# 8_Inputs_8_Outputs_Card.net
KiCad netlist of a schematic drawn in EasyEDA
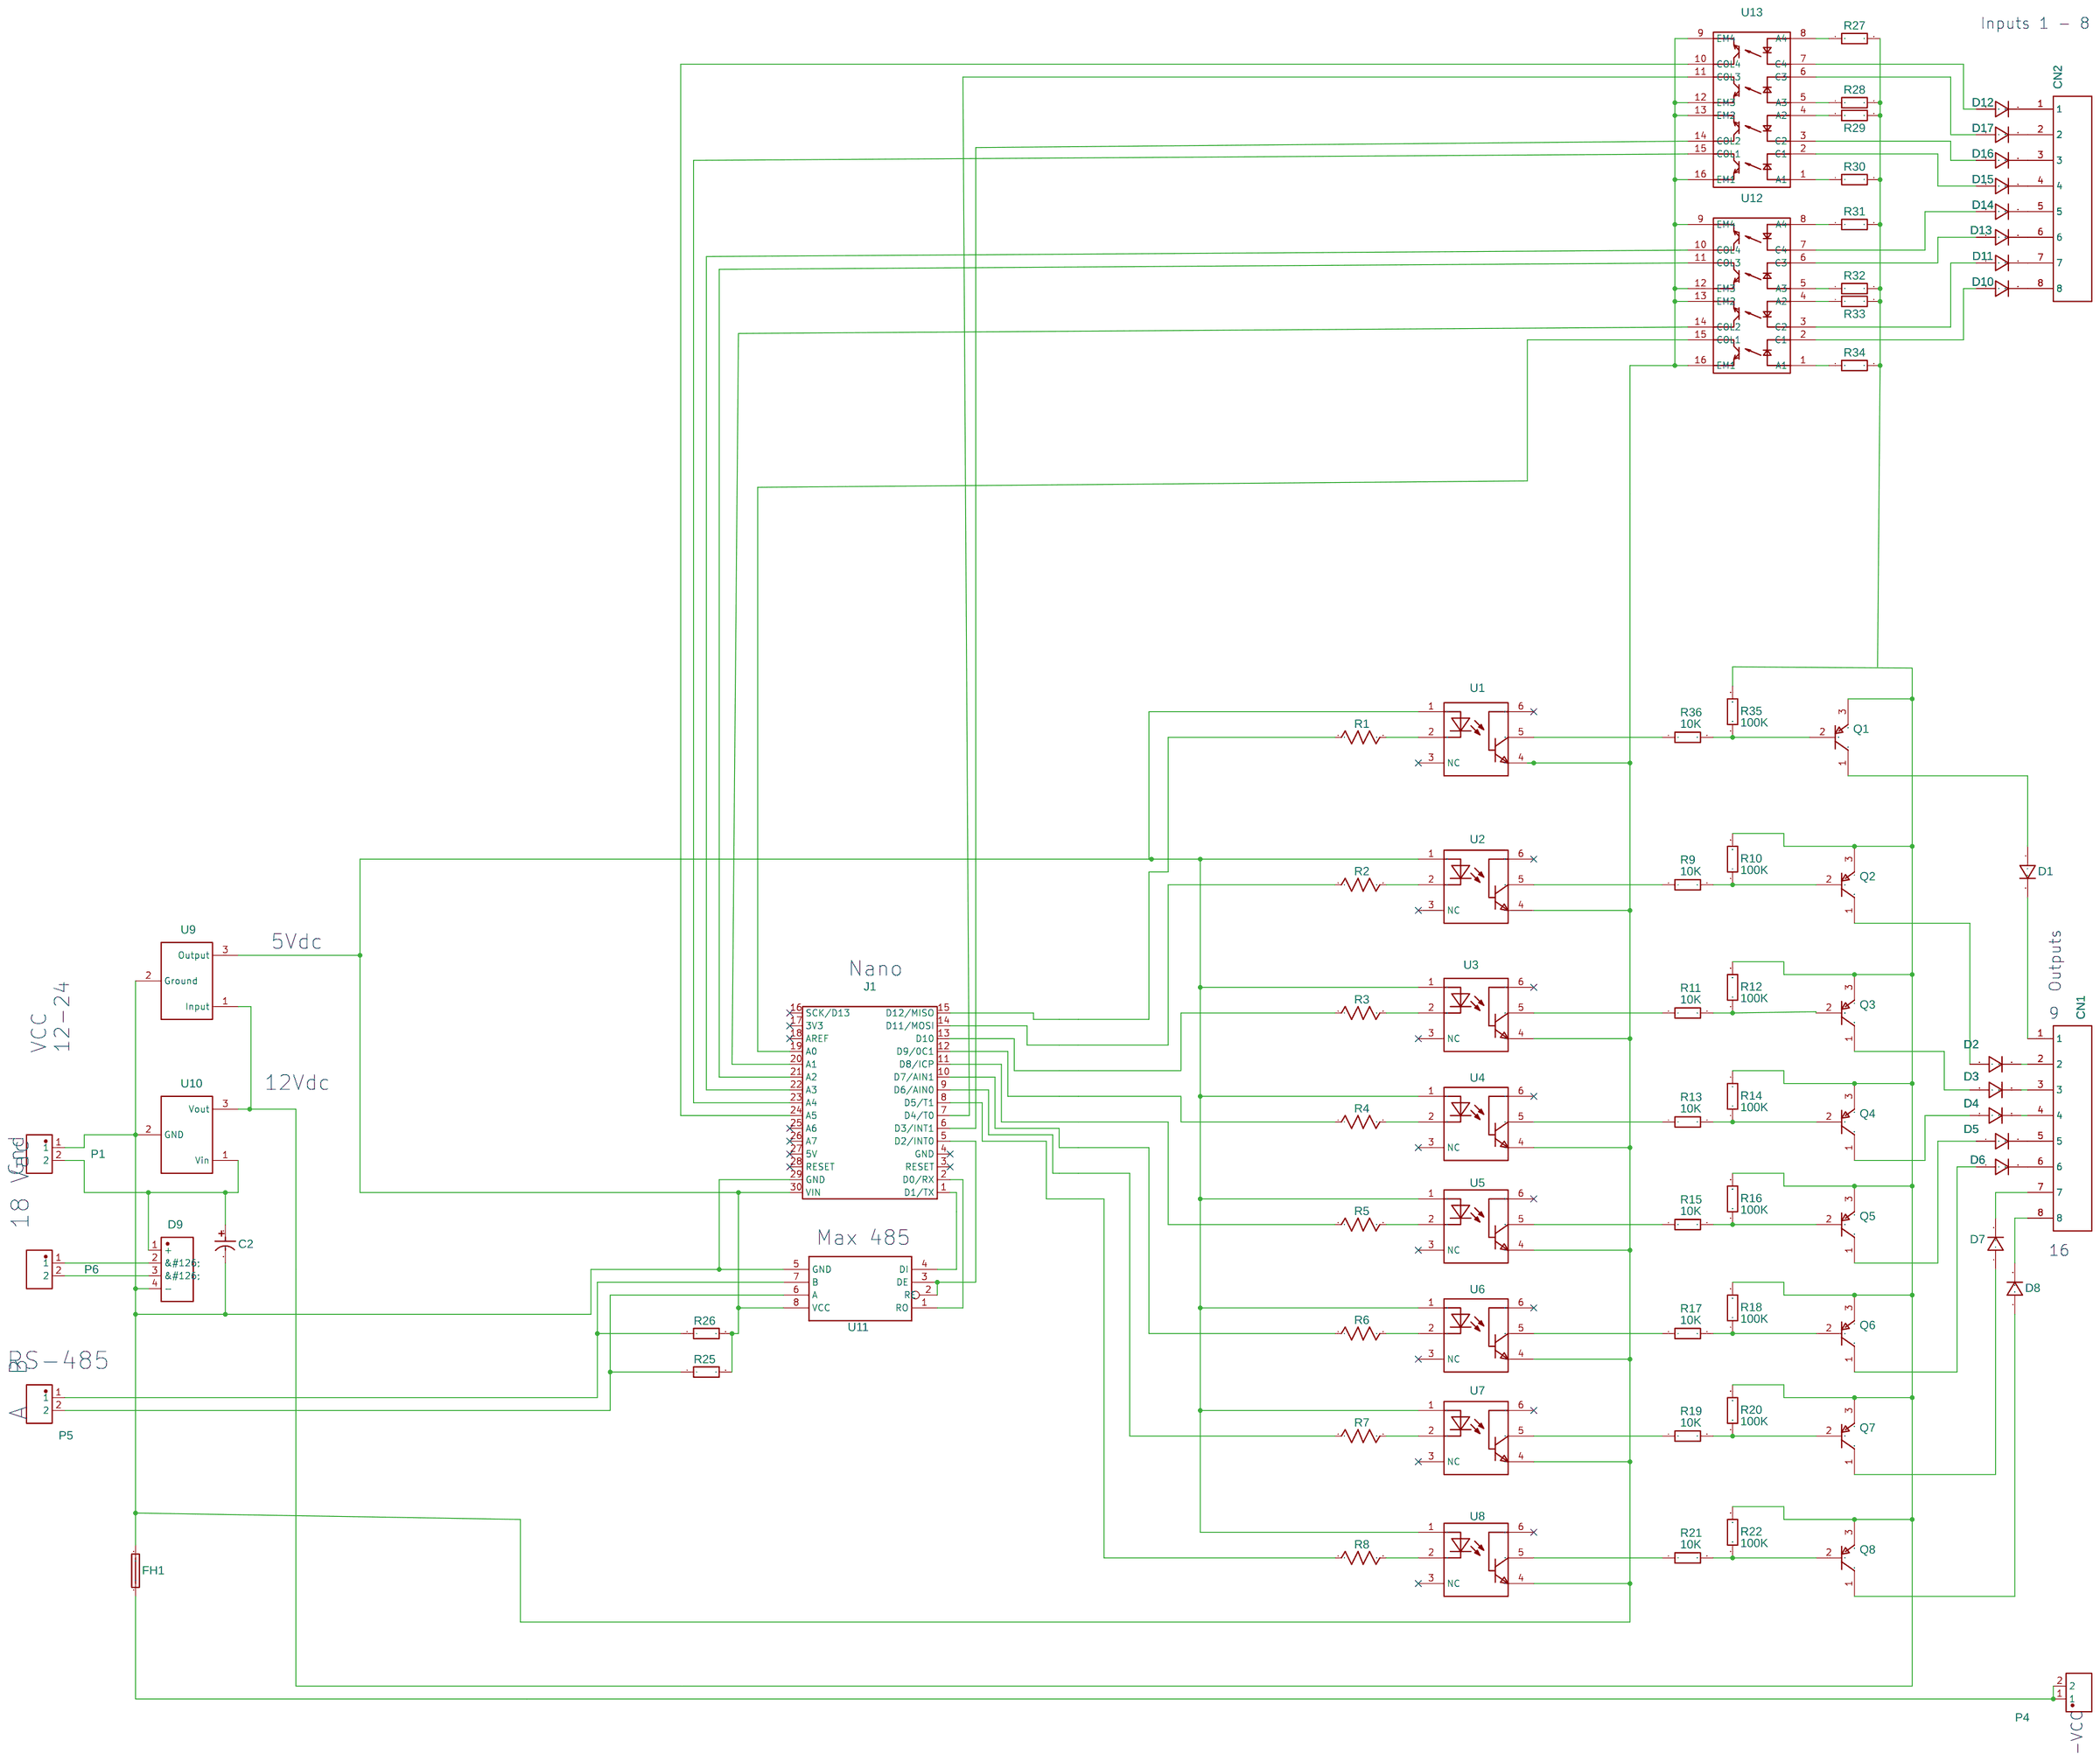
[diagram p0: schematic sheet]

(export (version "E")
  (design (tool "Eeschema 10.0.6"))
  (components
    (comp (ref "C2")
      (value "470uF")
      (fields
        (field (name "BOM_Manufacturer Part") "470uF 100V 16*25")
        (field (name "BOM_Supplier Part") "C72551")
      )
      (libsource (lib "") (part "470uF 100V 16*25"))
    )
    (comp (ref "CN1")
      (value "WJ25C-B-7.62-8P-13-00A")
      (fields (field (name "BOM_Supplier Part") "C49492"))
      (libsource (lib "") (part "Unknown_1530_395"))
    )
    (comp (ref "CN2")
      (value "WJ25C-B-7.62-8P-13-00A")
      (fields (field (name "BOM_Supplier Part") "C49492"))
      (libsource (lib "") (part "Unknown_1530_-330"))
    )
    (comp (ref "D1")
      (value "1N4001")
      (fields (field (name "BOM_Supplier Part") "C169150"))
      (libsource (lib "") (part "Unknown_1510_195"))
    )
    (comp (ref "D2")
      (value "1N4001")
      (fields (field (name "BOM_Supplier Part") "C169150"))
      (libsource (lib "") (part "Unknown_1485_345"))
    )
    (comp (ref "D3")
      (value "1N4001")
      (fields (field (name "BOM_Supplier Part") "C169150"))
      (libsource (lib "") (part "Unknown_1485_365"))
    )
    (comp (ref "D4")
      (value "1N4001")
      (fields (field (name "BOM_Supplier Part") "C169150"))
      (libsource (lib "") (part "Unknown_1485_385"))
    )
    (comp (ref "D5")
      (value "1N4001")
      (fields (field (name "BOM_Supplier Part") "C169150"))
      (libsource (lib "") (part "Unknown_1490_405"))
    )
    (comp (ref "D6")
      (value "1N4001")
      (fields (field (name "BOM_Supplier Part") "C169150"))
      (libsource (lib "") (part "Unknown_1490_425"))
    )
    (comp (ref "D7")
      (value "1N4001")
      (fields (field (name "BOM_Supplier Part") "C169150"))
      (libsource (lib "") (part "Unknown_1485_485"))
    )
    (comp (ref "D8")
      (value "1N4001")
      (fields (field (name "BOM_Supplier Part") "C169150"))
      (libsource (lib "") (part "Unknown_1500_520"))
    )
    (comp (ref "D9")
      (value "D50SB100")
      (fields (field (name "BOM_Supplier Part") "C411148"))
      (libsource (lib "") (part "Unknown_60_505"))
    )
    (comp (ref "D10")
      (value "1N4001")
      (fields (field (name "BOM_Supplier Part") "C169150"))
      (libsource (lib "") (part "Unknown_1490_-260"))
    )
    (comp (ref "D11")
      (value "1N4001")
      (fields (field (name "BOM_Supplier Part") "C169150"))
      (libsource (lib "") (part "Unknown_1490_-280"))
    )
    (comp (ref "D12")
      (value "1N4001")
      (fields (field (name "BOM_Supplier Part") "C169150"))
      (libsource (lib "") (part "Unknown_1490_-400"))
    )
    (comp (ref "D13")
      (value "1N4001")
      (fields (field (name "BOM_Supplier Part") "C169150"))
      (libsource (lib "") (part "Unknown_1490_-300"))
    )
    (comp (ref "D14")
      (value "1N4001")
      (fields (field (name "BOM_Supplier Part") "C169150"))
      (libsource (lib "") (part "Unknown_1490_-320"))
    )
    (comp (ref "D15")
      (value "1N4001")
      (fields (field (name "BOM_Supplier Part") "C169150"))
      (libsource (lib "") (part "Unknown_1490_-340"))
    )
    (comp (ref "D16")
      (value "1N4001")
      (fields (field (name "BOM_Supplier Part") "C169150"))
      (libsource (lib "") (part "Unknown_1490_-360"))
    )
    (comp (ref "D17")
      (value "1N4001")
      (fields (field (name "BOM_Supplier Part") "C169150"))
      (libsource (lib "") (part "Unknown_1490_-380"))
    )
    (comp (ref "FH1")
      (value "64600001003")
      (fields (field (name "BOM_Supplier Part") "C206887"))
      (libsource (lib "") (part "Unknown_35_740"))
    )
    (comp (ref "J1") (value "Arduino_Nano_Header") (libsource (lib "") (part "Unknown_605_375")))
    (comp (ref "P1")
      (value "WJ25C-B-2P")
      (fields (field (name "BOM_Supplier Part") "C8422"))
      (libsource (lib "") (part "Unknown_-40_415"))
    )
    (comp (ref "P4")
      (value "WJ25C-B-2P")
      (fields (field (name "BOM_Supplier Part") "C8422"))
      (libsource (lib "") (part "Unknown_1550_835"))
    )
    (comp (ref "P5")
      (value "WJ25C-B-2P")
      (fields (field (name "BOM_Supplier Part") "C8422"))
      (libsource (lib "") (part "Unknown_-40_610"))
    )
    (comp (ref "P6")
      (value "WJ25C-B-2P")
      (fields (field (name "BOM_Supplier Part") "C8422"))
      (libsource (lib "") (part "Unknown_-40_505"))
    )
    (comp (ref "Q1")
      (value "2N4033")
      (fields (field (name "BOM_Supplier Part") "610-2N4033"))
      (libsource (lib "") (part "Unknown_1355_90"))
    )
    (comp (ref "Q2")
      (value "2N4033")
      (fields (field (name "BOM_Supplier Part") "610-2N4033"))
      (libsource (lib "") (part "Unknown_1360_205"))
    )
    (comp (ref "Q3")
      (value "2N4033")
      (fields (field (name "BOM_Supplier Part") "610-2N4033"))
      (libsource (lib "") (part "Unknown_1360_305"))
    )
    (comp (ref "Q4")
      (value "2N4033")
      (fields (field (name "BOM_Supplier Part") "610-2N4033"))
      (libsource (lib "") (part "Unknown_1360_390"))
    )
    (comp (ref "Q5")
      (value "2N4033")
      (fields (field (name "BOM_Supplier Part") "610-2N4033"))
      (libsource (lib "") (part "Unknown_1360_470"))
    )
    (comp (ref "Q6")
      (value "2N4033")
      (fields (field (name "BOM_Supplier Part") "610-2N4033"))
      (libsource (lib "") (part "Unknown_1360_555"))
    )
    (comp (ref "Q7")
      (value "2N4033")
      (fields (field (name "BOM_Supplier Part") "610-2N4033"))
      (libsource (lib "") (part "Unknown_1360_635"))
    )
    (comp (ref "Q8")
      (value "2N4033")
      (fields (field (name "BOM_Supplier Part") "610-2N4033"))
      (libsource (lib "") (part "Unknown_1360_730"))
    )
    (comp (ref "R1")
      (value "1k")
      (fields
        (field (name "BOM_Manufacturer Part") "MFR0W4F1001A50")
        (field (name "BOM_Supplier Part") "C57435")
      )
      (libsource (lib "") (part "Res_AXIAL-0.3(1/8W)_US"))
    )
    (comp (ref "R2")
      (value "1k")
      (fields
        (field (name "BOM_Manufacturer Part") "MFR0W4F1001A50")
        (field (name "BOM_Supplier Part") "C57435")
      )
      (libsource (lib "") (part "Res_AXIAL-0.3(1/8W)_US"))
    )
    (comp (ref "R3")
      (value "1k")
      (fields
        (field (name "BOM_Manufacturer Part") "MFR0W4F1001A50")
        (field (name "BOM_Supplier Part") "C57435")
      )
      (libsource (lib "") (part "Res_AXIAL-0.3(1/8W)_US"))
    )
    (comp (ref "R4")
      (value "1k")
      (fields
        (field (name "BOM_Manufacturer Part") "MFR0W4F1001A50")
        (field (name "BOM_Supplier Part") "C57435")
      )
      (libsource (lib "") (part "Res_AXIAL-0.3(1/8W)_US"))
    )
    (comp (ref "R5")
      (value "1k")
      (fields
        (field (name "BOM_Manufacturer Part") "MFR0W4F1001A50")
        (field (name "BOM_Supplier Part") "C57435")
      )
      (libsource (lib "") (part "Res_AXIAL-0.3(1/8W)_US"))
    )
    (comp (ref "R6")
      (value "1k")
      (fields
        (field (name "BOM_Manufacturer Part") "MFR0W4F1001A50")
        (field (name "BOM_Supplier Part") "C57435")
      )
      (libsource (lib "") (part "Res_AXIAL-0.3(1/8W)_US"))
    )
    (comp (ref "R7")
      (value "1k")
      (fields
        (field (name "BOM_Manufacturer Part") "MFR0W4F1001A50")
        (field (name "BOM_Supplier Part") "C57435")
      )
      (libsource (lib "") (part "Res_AXIAL-0.3(1/8W)_US"))
    )
    (comp (ref "R8")
      (value "1k")
      (fields
        (field (name "BOM_Manufacturer Part") "MFR0W4F1001A50")
        (field (name "BOM_Supplier Part") "C57435")
      )
      (libsource (lib "") (part "Res_AXIAL-0.3(1/8W)_US"))
    )
    (comp (ref "R9")
      (value "10K")
      (fields
        (field (name "BOM_Manufacturer Part") "CFR0W4J0103A50")
        (field (name "BOM_Supplier Part") "C61299")
      )
      (libsource (lib "") (part "CFR0W4J0103A50"))
    )
    (comp (ref "R10")
      (value "100K")
      (fields
        (field (name "BOM_Manufacturer Part") "CFR0W4J0104A50")
        (field (name "BOM_Supplier Part") "C61303")
      )
      (libsource (lib "") (part "CFR0W4J0104A50"))
    )
    (comp (ref "R11")
      (value "10K")
      (fields
        (field (name "BOM_Manufacturer Part") "CFR0W4J0103A50")
        (field (name "BOM_Supplier Part") "C61299")
      )
      (libsource (lib "") (part "CFR0W4J0103A50"))
    )
    (comp (ref "R12")
      (value "100K")
      (fields
        (field (name "BOM_Manufacturer Part") "CFR0W4J0104A50")
        (field (name "BOM_Supplier Part") "C61303")
      )
      (libsource (lib "") (part "CFR0W4J0104A50"))
    )
    (comp (ref "R13")
      (value "10K")
      (fields
        (field (name "BOM_Manufacturer Part") "CFR0W4J0103A50")
        (field (name "BOM_Supplier Part") "C61299")
      )
      (libsource (lib "") (part "CFR0W4J0103A50"))
    )
    (comp (ref "R14")
      (value "100K")
      (fields
        (field (name "BOM_Manufacturer Part") "CFR0W4J0104A50")
        (field (name "BOM_Supplier Part") "C61303")
      )
      (libsource (lib "") (part "CFR0W4J0104A50"))
    )
    (comp (ref "R15")
      (value "10K")
      (fields
        (field (name "BOM_Manufacturer Part") "CFR0W4J0103A50")
        (field (name "BOM_Supplier Part") "C61299")
      )
      (libsource (lib "") (part "CFR0W4J0103A50"))
    )
    (comp (ref "R16")
      (value "100K")
      (fields
        (field (name "BOM_Manufacturer Part") "CFR0W4J0104A50")
        (field (name "BOM_Supplier Part") "C61303")
      )
      (libsource (lib "") (part "CFR0W4J0104A50"))
    )
    (comp (ref "R17")
      (value "10K")
      (fields
        (field (name "BOM_Manufacturer Part") "CFR0W4J0103A50")
        (field (name "BOM_Supplier Part") "C61299")
      )
      (libsource (lib "") (part "CFR0W4J0103A50"))
    )
    (comp (ref "R18")
      (value "100K")
      (fields
        (field (name "BOM_Manufacturer Part") "CFR0W4J0104A50")
        (field (name "BOM_Supplier Part") "C61303")
      )
      (libsource (lib "") (part "CFR0W4J0104A50"))
    )
    (comp (ref "R19")
      (value "10K")
      (fields
        (field (name "BOM_Manufacturer Part") "CFR0W4J0103A50")
        (field (name "BOM_Supplier Part") "C61299")
      )
      (libsource (lib "") (part "CFR0W4J0103A50"))
    )
    (comp (ref "R20")
      (value "100K")
      (fields
        (field (name "BOM_Manufacturer Part") "CFR0W4J0104A50")
        (field (name "BOM_Supplier Part") "C61303")
      )
      (libsource (lib "") (part "CFR0W4J0104A50"))
    )
    (comp (ref "R21")
      (value "10K")
      (fields
        (field (name "BOM_Manufacturer Part") "CFR0W4J0103A50")
        (field (name "BOM_Supplier Part") "C61299")
      )
      (libsource (lib "") (part "CFR0W4J0103A50"))
    )
    (comp (ref "R22")
      (value "100K")
      (fields
        (field (name "BOM_Manufacturer Part") "CFR0W4J0104A50")
        (field (name "BOM_Supplier Part") "C61303")
      )
      (libsource (lib "") (part "CFR0W4J0104A50"))
    )
    (comp (ref "R25")
      (value "10K")
      (fields
        (field (name "BOM_Manufacturer Part") "CFR0W4J0103A50")
        (field (name "BOM_Supplier Part") "C61299")
      )
      (libsource (lib "") (part "CFR0W4J0103A50"))
    )
    (comp (ref "R26")
      (value "10K")
      (fields
        (field (name "BOM_Manufacturer Part") "CFR0W4J0103A50")
        (field (name "BOM_Supplier Part") "C61299")
      )
      (libsource (lib "") (part "CFR0W4J0103A50"))
    )
    (comp (ref "R27")
      (value "220")
      (fields
        (field (name "BOM_Manufacturer Part") "CFR0W4J0221A50")
        (field (name "BOM_Supplier Part") "C61289")
      )
      (libsource (lib "") (part "CFR0W4J0221A50"))
    )
    (comp (ref "R28")
      (value "220")
      (fields
        (field (name "BOM_Manufacturer Part") "CFR0W4J0221A50")
        (field (name "BOM_Supplier Part") "C61289")
      )
      (libsource (lib "") (part "CFR0W4J0221A50"))
    )
    (comp (ref "R29")
      (value "220")
      (fields
        (field (name "BOM_Manufacturer Part") "CFR0W4J0221A50")
        (field (name "BOM_Supplier Part") "C61289")
      )
      (libsource (lib "") (part "CFR0W4J0221A50"))
    )
    (comp (ref "R30")
      (value "220")
      (fields
        (field (name "BOM_Manufacturer Part") "CFR0W4J0221A50")
        (field (name "BOM_Supplier Part") "C61289")
      )
      (libsource (lib "") (part "CFR0W4J0221A50"))
    )
    (comp (ref "R31")
      (value "220")
      (fields
        (field (name "BOM_Manufacturer Part") "CFR0W4J0221A50")
        (field (name "BOM_Supplier Part") "C61289")
      )
      (libsource (lib "") (part "CFR0W4J0221A50"))
    )
    (comp (ref "R32")
      (value "220")
      (fields
        (field (name "BOM_Manufacturer Part") "CFR0W4J0221A50")
        (field (name "BOM_Supplier Part") "C61289")
      )
      (libsource (lib "") (part "CFR0W4J0221A50"))
    )
    (comp (ref "R33")
      (value "220")
      (fields
        (field (name "BOM_Manufacturer Part") "CFR0W4J0221A50")
        (field (name "BOM_Supplier Part") "C61289")
      )
      (libsource (lib "") (part "CFR0W4J0221A50"))
    )
    (comp (ref "R34")
      (value "220")
      (fields
        (field (name "BOM_Manufacturer Part") "CFR0W4J0221A50")
        (field (name "BOM_Supplier Part") "C61289")
      )
      (libsource (lib "") (part "CFR0W4J0221A50"))
    )
    (comp (ref "R35")
      (value "100K")
      (fields
        (field (name "BOM_Manufacturer Part") "CFR0W4J0104A50")
        (field (name "BOM_Supplier Part") "C61303")
      )
      (libsource (lib "") (part "CFR0W4J0104A50"))
    )
    (comp (ref "R36")
      (value "10K")
      (fields
        (field (name "BOM_Manufacturer Part") "CFR0W4J0103A50")
        (field (name "BOM_Supplier Part") "C61299")
      )
      (libsource (lib "") (part "CFR0W4J0103A50"))
    )
    (comp (ref "U1")
      (value "4N25M")
      (fields (field (name "BOM_Supplier Part") "C5241"))
      (libsource (lib "") (part "Unknown_1080_90"))
    )
    (comp (ref "U2")
      (value "4N25M")
      (fields (field (name "BOM_Supplier Part") "C5241"))
      (libsource (lib "") (part "Unknown_1080_205"))
    )
    (comp (ref "U3")
      (value "4N25M")
      (fields (field (name "BOM_Supplier Part") "C5241"))
      (libsource (lib "") (part "Unknown_1080_305"))
    )
    (comp (ref "U4")
      (value "4N25M")
      (fields (field (name "BOM_Supplier Part") "C5241"))
      (libsource (lib "") (part "Unknown_1080_390"))
    )
    (comp (ref "U5")
      (value "4N25M")
      (fields (field (name "BOM_Supplier Part") "C5241"))
      (libsource (lib "") (part "Unknown_1080_470"))
    )
    (comp (ref "U6")
      (value "4N25M")
      (fields (field (name "BOM_Supplier Part") "C5241"))
      (libsource (lib "") (part "Unknown_1080_555"))
    )
    (comp (ref "U7")
      (value "4N25M")
      (fields (field (name "BOM_Supplier Part") "C5241"))
      (libsource (lib "") (part "Unknown_1080_635"))
    )
    (comp (ref "U8")
      (value "4N25M")
      (fields (field (name "BOM_Supplier Part") "C5241"))
      (libsource (lib "") (part "Unknown_1080_730"))
    )
    (comp (ref "U9")
      (value "MC7805BTG")
      (fields (field (name "BOM_Supplier Part") "C45385"))
      (libsource (lib "") (part "Unknown_75_280"))
    )
    (comp (ref "U10")
      (value "CJ7812")
      (fields (field (name "BOM_Supplier Part") "C77894"))
      (libsource (lib "") (part "Unknown_75_400"))
    )
    (comp (ref "U11") (value "MAX485DIL") (libsource (lib "") (part "Unknown_600_520")))
    (comp (ref "U12")
      (value "ILQ2")
      (fields (field (name "BOM_Supplier Part") "C145338"))
      (libsource (lib "") (part "ILQ2"))
    )
    (comp (ref "U13")
      (value "ILQ2")
      (fields (field (name "BOM_Supplier Part") "C145338"))
      (libsource (lib "") (part "ILQ2"))
    )
  )
  (nets
    (net (code "1") (name "Net-(CN1-Pad1)") (class "Default")
      (node (ref "CN1") (pin "1") (pinfunction "1_1") (pintype "input"))
      (node (ref "D1") (pin "2") (pinfunction "2_2") (pintype "unspecified"))
    )
    (net (code "2") (name "Net-(CN1-Pad2)") (class "Default")
      (node (ref "CN1") (pin "2") (pinfunction "2_2") (pintype "input"))
      (node (ref "D2") (pin "2") (pinfunction "2_2") (pintype "unspecified"))
    )
    (net (code "3") (name "Net-(CN1-Pad3)") (class "Default")
      (node (ref "CN1") (pin "3") (pinfunction "3_3") (pintype "input"))
      (node (ref "D3") (pin "2") (pinfunction "2_2") (pintype "unspecified"))
    )
    (net (code "4") (name "Net-(CN1-Pad4)") (class "Default")
      (node (ref "CN1") (pin "4") (pinfunction "4_4") (pintype "input"))
      (node (ref "D4") (pin "2") (pinfunction "2_2") (pintype "unspecified"))
    )
    (net (code "5") (name "Net-(CN1-Pad5)") (class "Default")
      (node (ref "CN1") (pin "5") (pinfunction "5_5") (pintype "input"))
      (node (ref "D5") (pin "2") (pinfunction "2_2") (pintype "unspecified"))
    )
    (net (code "6") (name "Net-(CN1-Pad6)") (class "Default")
      (node (ref "CN1") (pin "6") (pinfunction "6_6") (pintype "input"))
      (node (ref "D6") (pin "2") (pinfunction "2_2") (pintype "unspecified"))
    )
    (net (code "7") (name "Net-(CN1-Pad7)") (class "Default")
      (node (ref "CN1") (pin "7") (pinfunction "7_7") (pintype "input"))
      (node (ref "D7") (pin "2") (pinfunction "2_2") (pintype "unspecified"))
    )
    (net (code "8") (name "Net-(CN1-Pad8)") (class "Default")
      (node (ref "CN1") (pin "8") (pinfunction "8_8") (pintype "input"))
      (node (ref "D8") (pin "2") (pinfunction "2_2") (pintype "unspecified"))
    )
    (net (code "9") (name "Net-(CN2-Pad1)") (class "Default")
      (node (ref "CN2") (pin "1") (pinfunction "1_1") (pintype "input"))
      (node (ref "D12") (pin "2") (pinfunction "2_2") (pintype "unspecified"))
    )
    (net (code "10") (name "Net-(CN2-Pad2)") (class "Default")
      (node (ref "CN2") (pin "2") (pinfunction "2_2") (pintype "input"))
      (node (ref "D17") (pin "2") (pinfunction "2_2") (pintype "unspecified"))
    )
    (net (code "11") (name "Net-(CN2-Pad3)") (class "Default")
      (node (ref "CN2") (pin "3") (pinfunction "3_3") (pintype "input"))
      (node (ref "D16") (pin "2") (pinfunction "2_2") (pintype "unspecified"))
    )
    (net (code "12") (name "Net-(CN2-Pad4)") (class "Default")
      (node (ref "CN2") (pin "4") (pinfunction "4_4") (pintype "input"))
      (node (ref "D15") (pin "2") (pinfunction "2_2") (pintype "unspecified"))
    )
    (net (code "13") (name "Net-(CN2-Pad5)") (class "Default")
      (node (ref "CN2") (pin "5") (pinfunction "5_5") (pintype "input"))
      (node (ref "D14") (pin "2") (pinfunction "2_2") (pintype "unspecified"))
    )
    (net (code "14") (name "Net-(CN2-Pad6)") (class "Default")
      (node (ref "CN2") (pin "6") (pinfunction "6_6") (pintype "input"))
      (node (ref "D13") (pin "2") (pinfunction "2_2") (pintype "unspecified"))
    )
    (net (code "15") (name "Net-(CN2-Pad7)") (class "Default")
      (node (ref "CN2") (pin "7") (pinfunction "7_7") (pintype "input"))
      (node (ref "D11") (pin "2") (pinfunction "2_2") (pintype "unspecified"))
    )
    (net (code "16") (name "Net-(CN2-Pad8)") (class "Default")
      (node (ref "CN2") (pin "8") (pinfunction "8_8") (pintype "input"))
      (node (ref "D10") (pin "2") (pinfunction "2_2") (pintype "unspecified"))
    )
    (net (code "17") (name "Net-(D9-&#126;-Pad2)") (class "Default")
      (node (ref "D9") (pin "2") (pinfunction "&#126;_2") (pintype "unspecified"))
      (node (ref "P6") (pin "1") (pinfunction "1_1") (pintype "unspecified"))
    )
    (net (code "18") (name "Net-(D9-&#126;-Pad3)") (class "Default")
      (node (ref "D9") (pin "3") (pinfunction "&#126;_3") (pintype "unspecified"))
      (node (ref "P6") (pin "2") (pinfunction "2_2") (pintype "unspecified"))
    )
    (net (code "19") (name "Net-(D9-+)") (class "Default")
      (node (ref "C2") (pin "1") (pinfunction "1_1") (pintype "input"))
      (node (ref "D9") (pin "1") (pinfunction "+_1") (pintype "unspecified"))
      (node (ref "P1") (pin "2") (pinfunction "2_2") (pintype "unspecified"))
      (node (ref "U10") (pin "1") (pinfunction "Vin_1") (pintype "unspecified"))
    )
    (net (code "20") (name "Net-(D9--)") (class "Default")
      (node (ref "C2") (pin "2") (pinfunction "2_2") (pintype "input"))
      (node (ref "D9") (pin "4") (pinfunction "-_4") (pintype "unspecified"))
      (node (ref "FH1") (pin "2") (pinfunction "2_2") (pintype "unspecified"))
      (node (ref "J1") (pin "29") (pinfunction "GND_29") (pintype "unspecified"))
      (node (ref "P1") (pin "1") (pinfunction "1_1") (pintype "unspecified"))
      (node (ref "U1") (pin "4") (pinfunction "4_4") (pintype "unspecified"))
      (node (ref "U10") (pin "2") (pinfunction "GND_2") (pintype "unspecified"))
      (node (ref "U11") (pin "5") (pinfunction "GND_5") (pintype "unspecified"))
      (node (ref "U12") (pin "12") (pinfunction "EM3_12") (pintype "unspecified"))
      (node (ref "U12") (pin "13") (pinfunction "EM2_13") (pintype "unspecified"))
      (node (ref "U12") (pin "16") (pinfunction "EM1_16") (pintype "unspecified"))
      (node (ref "U12") (pin "9") (pinfunction "EM4_9") (pintype "unspecified"))
      (node (ref "U13") (pin "12") (pinfunction "EM3_12") (pintype "unspecified"))
      (node (ref "U13") (pin "13") (pinfunction "EM2_13") (pintype "unspecified"))
      (node (ref "U13") (pin "16") (pinfunction "EM1_16") (pintype "unspecified"))
      (node (ref "U13") (pin "9") (pinfunction "EM4_9") (pintype "unspecified"))
      (node (ref "U2") (pin "4") (pinfunction "4_4") (pintype "unspecified"))
      (node (ref "U3") (pin "4") (pinfunction "4_4") (pintype "unspecified"))
      (node (ref "U4") (pin "4") (pinfunction "4_4") (pintype "unspecified"))
      (node (ref "U5") (pin "4") (pinfunction "4_4") (pintype "unspecified"))
      (node (ref "U6") (pin "4") (pinfunction "4_4") (pintype "unspecified"))
      (node (ref "U7") (pin "4") (pinfunction "4_4") (pintype "unspecified"))
      (node (ref "U8") (pin "4") (pinfunction "4_4") (pintype "unspecified"))
      (node (ref "U9") (pin "2") (pinfunction "Ground_2") (pintype "unspecified"))
    )
    (net (code "21") (name "Net-(FH1-Pad1)") (class "Default")
      (node (ref "FH1") (pin "1") (pinfunction "1_1") (pintype "unspecified"))
      (node (ref "P4") (pin "1") (pinfunction "1_1") (pintype "unspecified"))
      (node (ref "P4") (pin "2") (pinfunction "2_2") (pintype "unspecified"))
    )
    (net (code "22") (name "Net-(J1-A0)") (class "Default")
      (node (ref "J1") (pin "19") (pinfunction "A0_19") (pintype "unspecified"))
      (node (ref "U12") (pin "15") (pinfunction "COL1_15") (pintype "unspecified"))
    )
    (net (code "23") (name "Net-(J1-A1)") (class "Default")
      (node (ref "J1") (pin "20") (pinfunction "A1_20") (pintype "unspecified"))
      (node (ref "U12") (pin "14") (pinfunction "COL2_14") (pintype "unspecified"))
    )
    (net (code "24") (name "Net-(J1-A2)") (class "Default")
      (node (ref "J1") (pin "21") (pinfunction "A2_21") (pintype "unspecified"))
      (node (ref "U12") (pin "11") (pinfunction "COL3_11") (pintype "unspecified"))
    )
    (net (code "25") (name "Net-(J1-A3)") (class "Default")
      (node (ref "J1") (pin "22") (pinfunction "A3_22") (pintype "unspecified"))
      (node (ref "U12") (pin "10") (pinfunction "COL4_10") (pintype "unspecified"))
    )
    (net (code "26") (name "Net-(J1-A4)") (class "Default")
      (node (ref "J1") (pin "23") (pinfunction "A4_23") (pintype "unspecified"))
      (node (ref "U13") (pin "15") (pinfunction "COL1_15") (pintype "unspecified"))
    )
    (net (code "27") (name "Net-(J1-A5)") (class "Default")
      (node (ref "J1") (pin "24") (pinfunction "A5_24") (pintype "unspecified"))
      (node (ref "U13") (pin "10") (pinfunction "COL4_10") (pintype "unspecified"))
    )
    (net (code "28") (name "Net-(J1-D0{slash}RX)") (class "Default")
      (node (ref "J1") (pin "2") (pinfunction "D0/RX_2") (pintype "unspecified"))
      (node (ref "U11") (pin "1") (pinfunction "RO_1") (pintype "unspecified"))
    )
    (net (code "29") (name "Net-(J1-D1{slash}TX)") (class "Default")
      (node (ref "J1") (pin "1") (pinfunction "D1/TX_1") (pintype "unspecified"))
      (node (ref "U11") (pin "4") (pinfunction "DI_4") (pintype "unspecified"))
    )
    (net (code "30") (name "Net-(J1-D2{slash}INT0)") (class "Default")
      (node (ref "J1") (pin "5") (pinfunction "D2/INT0_5") (pintype "unspecified"))
      (node (ref "U11") (pin "2") (pinfunction "RE_2") (pintype "unspecified"))
      (node (ref "U11") (pin "3") (pinfunction "DE_3") (pintype "unspecified"))
    )
    (net (code "31") (name "Net-(J1-D3{slash}INT1)") (class "Default")
      (node (ref "J1") (pin "6") (pinfunction "D3/INT1_6") (pintype "unspecified"))
      (node (ref "U13") (pin "14") (pinfunction "COL2_14") (pintype "unspecified"))
    )
    (net (code "32") (name "Net-(J1-D4{slash}T0)") (class "Default")
      (node (ref "J1") (pin "7") (pinfunction "D4/T0_7") (pintype "unspecified"))
      (node (ref "U13") (pin "11") (pinfunction "COL3_11") (pintype "unspecified"))
    )
    (net (code "33") (name "Net-(J1-D5{slash}T1)") (class "Default")
      (node (ref "J1") (pin "8") (pinfunction "D5/T1_8") (pintype "unspecified"))
      (node (ref "R8") (pin "1") (pinfunction "1_1") (pintype "unspecified"))
    )
    (net (code "34") (name "Net-(J1-D6{slash}AIN0)") (class "Default")
      (node (ref "J1") (pin "9") (pinfunction "D6/AIN0_9") (pintype "unspecified"))
      (node (ref "R7") (pin "1") (pinfunction "1_1") (pintype "unspecified"))
    )
    (net (code "35") (name "Net-(J1-D7{slash}AIN1)") (class "Default")
      (node (ref "J1") (pin "10") (pinfunction "D7/AIN1_10") (pintype "unspecified"))
      (node (ref "R6") (pin "1") (pinfunction "1_1") (pintype "unspecified"))
    )
    (net (code "36") (name "Net-(J1-D8{slash}ICP)") (class "Default")
      (node (ref "J1") (pin "11") (pinfunction "D8/ICP_11") (pintype "unspecified"))
      (node (ref "R5") (pin "1") (pinfunction "1_1") (pintype "unspecified"))
    )
    (net (code "37") (name "Net-(J1-D9{slash}0C1)") (class "Default")
      (node (ref "J1") (pin "12") (pinfunction "D9/0C1_12") (pintype "unspecified"))
      (node (ref "R4") (pin "1") (pinfunction "1_1") (pintype "unspecified"))
    )
    (net (code "38") (name "Net-(J1-D10)") (class "Default")
      (node (ref "J1") (pin "13") (pinfunction "D10_13") (pintype "unspecified"))
      (node (ref "R3") (pin "1") (pinfunction "1_1") (pintype "unspecified"))
    )
    (net (code "39") (name "Net-(J1-D11{slash}MOSI)") (class "Default")
      (node (ref "J1") (pin "14") (pinfunction "D11/MOSI_14") (pintype "unspecified"))
      (node (ref "R2") (pin "1") (pinfunction "1_1") (pintype "unspecified"))
    )
    (net (code "40") (name "Net-(J1-D12{slash}MISO)") (class "Default")
      (node (ref "J1") (pin "15") (pinfunction "D12/MISO_15") (pintype "unspecified"))
      (node (ref "R1") (pin "1") (pinfunction "1_1") (pintype "unspecified"))
    )
    (net (code "41") (name "Net-(J1-VIN)") (class "Default")
      (node (ref "J1") (pin "30") (pinfunction "VIN_30") (pintype "unspecified"))
      (node (ref "R25") (pin "2") (pinfunction "2_2") (pintype "input"))
      (node (ref "R26") (pin "2") (pinfunction "2_2") (pintype "input"))
      (node (ref "U1") (pin "1") (pinfunction "1_1") (pintype "unspecified"))
      (node (ref "U11") (pin "8") (pinfunction "VCC_8") (pintype "unspecified"))
      (node (ref "U2") (pin "1") (pinfunction "1_1") (pintype "unspecified"))
      (node (ref "U3") (pin "1") (pinfunction "1_1") (pintype "unspecified"))
      (node (ref "U4") (pin "1") (pinfunction "1_1") (pintype "unspecified"))
      (node (ref "U5") (pin "1") (pinfunction "1_1") (pintype "unspecified"))
      (node (ref "U6") (pin "1") (pinfunction "1_1") (pintype "unspecified"))
      (node (ref "U7") (pin "1") (pinfunction "1_1") (pintype "unspecified"))
      (node (ref "U8") (pin "1") (pinfunction "1_1") (pintype "unspecified"))
      (node (ref "U9") (pin "3") (pinfunction "Output_3") (pintype "unspecified"))
    )
    (net (code "42") (name "Net-(Q1-B)") (class "Default")
      (node (ref "Q1") (pin "2") (pinfunction "B_2") (pintype "unspecified"))
      (node (ref "R35") (pin "1") (pinfunction "1_1") (pintype "input"))
      (node (ref "R36") (pin "2") (pinfunction "2_2") (pintype "input"))
    )
    (net (code "43") (name "Net-(Q1-C)") (class "Default")
      (node (ref "D1") (pin "1") (pinfunction "1_1") (pintype "unspecified"))
      (node (ref "Q1") (pin "1") (pinfunction "C_1") (pintype "unspecified"))
    )
    (net (code "44") (name "Net-(Q1-E)") (class "Default")
      (node (ref "Q1") (pin "3") (pinfunction "E_3") (pintype "unspecified"))
      (node (ref "Q2") (pin "3") (pinfunction "E_3") (pintype "unspecified"))
      (node (ref "Q3") (pin "3") (pinfunction "E_3") (pintype "unspecified"))
      (node (ref "Q4") (pin "3") (pinfunction "E_3") (pintype "unspecified"))
      (node (ref "Q5") (pin "3") (pinfunction "E_3") (pintype "unspecified"))
      (node (ref "Q6") (pin "3") (pinfunction "E_3") (pintype "unspecified"))
      (node (ref "Q7") (pin "3") (pinfunction "E_3") (pintype "unspecified"))
      (node (ref "Q8") (pin "3") (pinfunction "E_3") (pintype "unspecified"))
      (node (ref "R10") (pin "2") (pinfunction "2_2") (pintype "input"))
      (node (ref "R12") (pin "2") (pinfunction "2_2") (pintype "input"))
      (node (ref "R14") (pin "2") (pinfunction "2_2") (pintype "input"))
      (node (ref "R16") (pin "2") (pinfunction "2_2") (pintype "input"))
      (node (ref "R18") (pin "2") (pinfunction "2_2") (pintype "input"))
      (node (ref "R20") (pin "2") (pinfunction "2_2") (pintype "input"))
      (node (ref "R22") (pin "2") (pinfunction "2_2") (pintype "input"))
      (node (ref "R35") (pin "2") (pinfunction "2_2") (pintype "input"))
      (node (ref "U10") (pin "3") (pinfunction "Vout_3") (pintype "unspecified"))
      (node (ref "U9") (pin "1") (pinfunction "Input_1") (pintype "unspecified"))
    )
    (net (code "45") (name "Net-(Q2-B)") (class "Default")
      (node (ref "Q2") (pin "2") (pinfunction "B_2") (pintype "unspecified"))
      (node (ref "R10") (pin "1") (pinfunction "1_1") (pintype "input"))
      (node (ref "R9") (pin "2") (pinfunction "2_2") (pintype "input"))
    )
    (net (code "46") (name "Net-(Q2-C)") (class "Default")
      (node (ref "D2") (pin "1") (pinfunction "1_1") (pintype "unspecified"))
      (node (ref "Q2") (pin "1") (pinfunction "C_1") (pintype "unspecified"))
    )
    (net (code "47") (name "Net-(Q3-B)") (class "Default")
      (node (ref "Q3") (pin "2") (pinfunction "B_2") (pintype "unspecified"))
      (node (ref "R11") (pin "2") (pinfunction "2_2") (pintype "input"))
      (node (ref "R12") (pin "1") (pinfunction "1_1") (pintype "input"))
    )
    (net (code "48") (name "Net-(Q3-C)") (class "Default")
      (node (ref "D3") (pin "1") (pinfunction "1_1") (pintype "unspecified"))
      (node (ref "Q3") (pin "1") (pinfunction "C_1") (pintype "unspecified"))
    )
    (net (code "49") (name "Net-(Q4-B)") (class "Default")
      (node (ref "Q4") (pin "2") (pinfunction "B_2") (pintype "unspecified"))
      (node (ref "R13") (pin "2") (pinfunction "2_2") (pintype "input"))
      (node (ref "R14") (pin "1") (pinfunction "1_1") (pintype "input"))
    )
    (net (code "50") (name "Net-(Q4-C)") (class "Default")
      (node (ref "D4") (pin "1") (pinfunction "1_1") (pintype "unspecified"))
      (node (ref "Q4") (pin "1") (pinfunction "C_1") (pintype "unspecified"))
    )
    (net (code "51") (name "Net-(Q5-B)") (class "Default")
      (node (ref "Q5") (pin "2") (pinfunction "B_2") (pintype "unspecified"))
      (node (ref "R15") (pin "2") (pinfunction "2_2") (pintype "input"))
      (node (ref "R16") (pin "1") (pinfunction "1_1") (pintype "input"))
    )
    (net (code "52") (name "Net-(Q5-C)") (class "Default")
      (node (ref "D5") (pin "1") (pinfunction "1_1") (pintype "unspecified"))
      (node (ref "Q5") (pin "1") (pinfunction "C_1") (pintype "unspecified"))
    )
    (net (code "53") (name "Net-(Q6-B)") (class "Default")
      (node (ref "Q6") (pin "2") (pinfunction "B_2") (pintype "unspecified"))
      (node (ref "R17") (pin "2") (pinfunction "2_2") (pintype "input"))
      (node (ref "R18") (pin "1") (pinfunction "1_1") (pintype "input"))
    )
    (net (code "54") (name "Net-(Q6-C)") (class "Default")
      (node (ref "D6") (pin "1") (pinfunction "1_1") (pintype "unspecified"))
      (node (ref "Q6") (pin "1") (pinfunction "C_1") (pintype "unspecified"))
    )
    (net (code "55") (name "Net-(Q7-B)") (class "Default")
      (node (ref "Q7") (pin "2") (pinfunction "B_2") (pintype "unspecified"))
      (node (ref "R19") (pin "2") (pinfunction "2_2") (pintype "input"))
      (node (ref "R20") (pin "1") (pinfunction "1_1") (pintype "input"))
    )
    (net (code "56") (name "Net-(Q7-C)") (class "Default")
      (node (ref "D7") (pin "1") (pinfunction "1_1") (pintype "unspecified"))
      (node (ref "Q7") (pin "1") (pinfunction "C_1") (pintype "unspecified"))
    )
    (net (code "57") (name "Net-(Q8-B)") (class "Default")
      (node (ref "Q8") (pin "2") (pinfunction "B_2") (pintype "unspecified"))
      (node (ref "R21") (pin "2") (pinfunction "2_2") (pintype "input"))
      (node (ref "R22") (pin "1") (pinfunction "1_1") (pintype "input"))
    )
    (net (code "58") (name "Net-(Q8-C)") (class "Default")
      (node (ref "D8") (pin "1") (pinfunction "1_1") (pintype "unspecified"))
      (node (ref "Q8") (pin "1") (pinfunction "C_1") (pintype "unspecified"))
    )
    (net (code "59") (name "Net-(R1-Pad2)") (class "Default")
      (node (ref "R1") (pin "2") (pinfunction "2_2") (pintype "unspecified"))
      (node (ref "U1") (pin "2") (pinfunction "2_2") (pintype "unspecified"))
    )
    (net (code "60") (name "Net-(R2-Pad2)") (class "Default")
      (node (ref "R2") (pin "2") (pinfunction "2_2") (pintype "unspecified"))
      (node (ref "U2") (pin "2") (pinfunction "2_2") (pintype "unspecified"))
    )
    (net (code "61") (name "Net-(R3-Pad2)") (class "Default")
      (node (ref "R3") (pin "2") (pinfunction "2_2") (pintype "unspecified"))
      (node (ref "U3") (pin "2") (pinfunction "2_2") (pintype "unspecified"))
    )
    (net (code "62") (name "Net-(R4-Pad2)") (class "Default")
      (node (ref "R4") (pin "2") (pinfunction "2_2") (pintype "unspecified"))
      (node (ref "U4") (pin "2") (pinfunction "2_2") (pintype "unspecified"))
    )
    (net (code "63") (name "Net-(R5-Pad2)") (class "Default")
      (node (ref "R5") (pin "2") (pinfunction "2_2") (pintype "unspecified"))
      (node (ref "U5") (pin "2") (pinfunction "2_2") (pintype "unspecified"))
    )
    (net (code "64") (name "Net-(R6-Pad2)") (class "Default")
      (node (ref "R6") (pin "2") (pinfunction "2_2") (pintype "unspecified"))
      (node (ref "U6") (pin "2") (pinfunction "2_2") (pintype "unspecified"))
    )
    (net (code "65") (name "Net-(R7-Pad2)") (class "Default")
      (node (ref "R7") (pin "2") (pinfunction "2_2") (pintype "unspecified"))
      (node (ref "U7") (pin "2") (pinfunction "2_2") (pintype "unspecified"))
    )
    (net (code "66") (name "Net-(R8-Pad2)") (class "Default")
      (node (ref "R8") (pin "2") (pinfunction "2_2") (pintype "unspecified"))
      (node (ref "U8") (pin "2") (pinfunction "2_2") (pintype "unspecified"))
    )
    (net (code "67") (name "Net-(R9-Pad1)") (class "Default")
      (node (ref "R9") (pin "1") (pinfunction "1_1") (pintype "input"))
      (node (ref "U2") (pin "5") (pinfunction "5_5") (pintype "unspecified"))
    )
    (net (code "68") (name "Net-(R11-Pad1)") (class "Default")
      (node (ref "R11") (pin "1") (pinfunction "1_1") (pintype "input"))
      (node (ref "U3") (pin "5") (pinfunction "5_5") (pintype "unspecified"))
    )
    (net (code "69") (name "Net-(R13-Pad1)") (class "Default")
      (node (ref "R13") (pin "1") (pinfunction "1_1") (pintype "input"))
      (node (ref "U4") (pin "5") (pinfunction "5_5") (pintype "unspecified"))
    )
    (net (code "70") (name "Net-(R15-Pad1)") (class "Default")
      (node (ref "R15") (pin "1") (pinfunction "1_1") (pintype "input"))
      (node (ref "U5") (pin "5") (pinfunction "5_5") (pintype "unspecified"))
    )
    (net (code "71") (name "Net-(R17-Pad1)") (class "Default")
      (node (ref "R17") (pin "1") (pinfunction "1_1") (pintype "input"))
      (node (ref "U6") (pin "5") (pinfunction "5_5") (pintype "unspecified"))
    )
    (net (code "72") (name "Net-(R19-Pad1)") (class "Default")
      (node (ref "R19") (pin "1") (pinfunction "1_1") (pintype "input"))
      (node (ref "U7") (pin "5") (pinfunction "5_5") (pintype "unspecified"))
    )
    (net (code "73") (name "Net-(R21-Pad1)") (class "Default")
      (node (ref "R21") (pin "1") (pinfunction "1_1") (pintype "input"))
      (node (ref "U8") (pin "5") (pinfunction "5_5") (pintype "unspecified"))
    )
    (net (code "74") (name "Net-(R27-Pad2)") (class "Default")
      (node (ref "R27") (pin "2") (pinfunction "2_2") (pintype "input"))
      (node (ref "R28") (pin "2") (pinfunction "2_2") (pintype "input"))
      (node (ref "R29") (pin "2") (pinfunction "2_2") (pintype "input"))
      (node (ref "R30") (pin "2") (pinfunction "2_2") (pintype "input"))
      (node (ref "R31") (pin "2") (pinfunction "2_2") (pintype "input"))
      (node (ref "R32") (pin "2") (pinfunction "2_2") (pintype "input"))
      (node (ref "R33") (pin "2") (pinfunction "2_2") (pintype "input"))
      (node (ref "R34") (pin "2") (pinfunction "2_2") (pintype "input"))
    )
    (net (code "75") (name "Net-(R36-Pad1)") (class "Default")
      (node (ref "R36") (pin "1") (pinfunction "1_1") (pintype "input"))
      (node (ref "U1") (pin "5") (pinfunction "5_5") (pintype "unspecified"))
    )
    (net (code "76") (name "Net-(U11-A)") (class "Default")
      (node (ref "P5") (pin "2") (pinfunction "2_2") (pintype "unspecified"))
      (node (ref "R25") (pin "1") (pinfunction "1_1") (pintype "input"))
      (node (ref "U11") (pin "6") (pinfunction "A_6") (pintype "unspecified"))
    )
    (net (code "77") (name "Net-(U11-B)") (class "Default")
      (node (ref "P5") (pin "1") (pinfunction "1_1") (pintype "unspecified"))
      (node (ref "R26") (pin "1") (pinfunction "1_1") (pintype "input"))
      (node (ref "U11") (pin "7") (pinfunction "B_7") (pintype "unspecified"))
    )
    (net (code "78") (name "Net-(U12-A1)") (class "Default")
      (node (ref "R34") (pin "1") (pinfunction "1_1") (pintype "input"))
      (node (ref "U12") (pin "1") (pinfunction "A1_1") (pintype "unspecified"))
    )
    (net (code "79") (name "Net-(U12-A2)") (class "Default")
      (node (ref "R33") (pin "1") (pinfunction "1_1") (pintype "input"))
      (node (ref "U12") (pin "4") (pinfunction "A2_4") (pintype "unspecified"))
    )
    (net (code "80") (name "Net-(U12-A3)") (class "Default")
      (node (ref "R32") (pin "1") (pinfunction "1_1") (pintype "input"))
      (node (ref "U12") (pin "5") (pinfunction "A3_5") (pintype "unspecified"))
    )
    (net (code "81") (name "Net-(U12-A4)") (class "Default")
      (node (ref "R31") (pin "1") (pinfunction "1_1") (pintype "input"))
      (node (ref "U12") (pin "8") (pinfunction "A4_8") (pintype "unspecified"))
    )
    (net (code "82") (name "Net-(U12-C1)") (class "Default")
      (node (ref "D10") (pin "1") (pinfunction "1_1") (pintype "unspecified"))
      (node (ref "U12") (pin "2") (pinfunction "C1_2") (pintype "unspecified"))
    )
    (net (code "83") (name "Net-(U12-C2)") (class "Default")
      (node (ref "D11") (pin "1") (pinfunction "1_1") (pintype "unspecified"))
      (node (ref "U12") (pin "3") (pinfunction "C2_3") (pintype "unspecified"))
    )
    (net (code "84") (name "Net-(U12-C3)") (class "Default")
      (node (ref "D13") (pin "1") (pinfunction "1_1") (pintype "unspecified"))
      (node (ref "U12") (pin "6") (pinfunction "C3_6") (pintype "unspecified"))
    )
    (net (code "85") (name "Net-(U12-C4)") (class "Default")
      (node (ref "D14") (pin "1") (pinfunction "1_1") (pintype "unspecified"))
      (node (ref "U12") (pin "7") (pinfunction "C4_7") (pintype "unspecified"))
    )
    (net (code "86") (name "Net-(U13-A1)") (class "Default")
      (node (ref "R30") (pin "1") (pinfunction "1_1") (pintype "input"))
      (node (ref "U13") (pin "1") (pinfunction "A1_1") (pintype "unspecified"))
    )
    (net (code "87") (name "Net-(U13-A2)") (class "Default")
      (node (ref "R29") (pin "1") (pinfunction "1_1") (pintype "input"))
      (node (ref "U13") (pin "4") (pinfunction "A2_4") (pintype "unspecified"))
    )
    (net (code "88") (name "Net-(U13-A3)") (class "Default")
      (node (ref "R28") (pin "1") (pinfunction "1_1") (pintype "input"))
      (node (ref "U13") (pin "5") (pinfunction "A3_5") (pintype "unspecified"))
    )
    (net (code "89") (name "Net-(U13-A4)") (class "Default")
      (node (ref "R27") (pin "1") (pinfunction "1_1") (pintype "input"))
      (node (ref "U13") (pin "8") (pinfunction "A4_8") (pintype "unspecified"))
    )
    (net (code "90") (name "Net-(U13-C1)") (class "Default")
      (node (ref "D15") (pin "1") (pinfunction "1_1") (pintype "unspecified"))
      (node (ref "U13") (pin "2") (pinfunction "C1_2") (pintype "unspecified"))
    )
    (net (code "91") (name "Net-(U13-C2)") (class "Default")
      (node (ref "D16") (pin "1") (pinfunction "1_1") (pintype "unspecified"))
      (node (ref "U13") (pin "3") (pinfunction "C2_3") (pintype "unspecified"))
    )
    (net (code "92") (name "Net-(U13-C3)") (class "Default")
      (node (ref "D17") (pin "1") (pinfunction "1_1") (pintype "unspecified"))
      (node (ref "U13") (pin "6") (pinfunction "C3_6") (pintype "unspecified"))
    )
    (net (code "93") (name "Net-(U13-C4)") (class "Default")
      (node (ref "D12") (pin "1") (pinfunction "1_1") (pintype "unspecified"))
      (node (ref "U13") (pin "7") (pinfunction "C4_7") (pintype "unspecified"))
    )
    (net (code "94") (name "unconnected-(J1-3V3-Pad17)") (class "Default")
      (node (ref "J1") (pin "17") (pinfunction "3V3_17") (pintype "unspecified+no_connect"))
    )
    (net (code "95") (name "unconnected-(J1-5V-Pad27)") (class "Default")
      (node (ref "J1") (pin "27") (pinfunction "5V_27") (pintype "unspecified+no_connect"))
    )
    (net (code "96") (name "unconnected-(J1-A6-Pad25)") (class "Default")
      (node (ref "J1") (pin "25") (pinfunction "A6_25") (pintype "unspecified+no_connect"))
    )
    (net (code "97") (name "unconnected-(J1-A7-Pad26)") (class "Default")
      (node (ref "J1") (pin "26") (pinfunction "A7_26") (pintype "unspecified+no_connect"))
    )
    (net (code "98") (name "unconnected-(J1-AREF-Pad18)") (class "Default")
      (node (ref "J1") (pin "18") (pinfunction "AREF_18") (pintype "unspecified+no_connect"))
    )
    (net (code "99") (name "unconnected-(J1-GND-Pad4)") (class "Default")
      (node (ref "J1") (pin "4") (pinfunction "GND_4") (pintype "unspecified+no_connect"))
    )
    (net (code "100") (name "unconnected-(J1-RESET-Pad3)") (class "Default")
      (node (ref "J1") (pin "3") (pinfunction "RESET_3") (pintype "unspecified+no_connect"))
    )
    (net (code "101") (name "unconnected-(J1-RESET-Pad28)") (class "Default")
      (node (ref "J1") (pin "28") (pinfunction "RESET_28") (pintype "unspecified+no_connect"))
    )
    (net (code "102") (name "unconnected-(J1-SCK{slash}D13-Pad16)") (class "Default")
      (node (ref "J1") (pin "16") (pinfunction "SCK/D13_16") (pintype "unspecified+no_connect"))
    )
    (net (code "103") (name "unconnected-(U1-NC-Pad3)") (class "Default")
      (node (ref "U1") (pin "3") (pinfunction "NC_3") (pintype "unspecified+no_connect"))
    )
    (net (code "104") (name "unconnected-(U1-Pad6)") (class "Default")
      (node (ref "U1") (pin "6") (pinfunction "6_6") (pintype "unspecified+no_connect"))
    )
    (net (code "105") (name "unconnected-(U2-NC-Pad3)") (class "Default")
      (node (ref "U2") (pin "3") (pinfunction "NC_3") (pintype "unspecified+no_connect"))
    )
    (net (code "106") (name "unconnected-(U2-Pad6)") (class "Default")
      (node (ref "U2") (pin "6") (pinfunction "6_6") (pintype "unspecified+no_connect"))
    )
    (net (code "107") (name "unconnected-(U3-NC-Pad3)") (class "Default")
      (node (ref "U3") (pin "3") (pinfunction "NC_3") (pintype "unspecified+no_connect"))
    )
    (net (code "108") (name "unconnected-(U3-Pad6)") (class "Default")
      (node (ref "U3") (pin "6") (pinfunction "6_6") (pintype "unspecified+no_connect"))
    )
    (net (code "109") (name "unconnected-(U4-NC-Pad3)") (class "Default")
      (node (ref "U4") (pin "3") (pinfunction "NC_3") (pintype "unspecified+no_connect"))
    )
    (net (code "110") (name "unconnected-(U4-Pad6)") (class "Default")
      (node (ref "U4") (pin "6") (pinfunction "6_6") (pintype "unspecified+no_connect"))
    )
    (net (code "111") (name "unconnected-(U5-NC-Pad3)") (class "Default")
      (node (ref "U5") (pin "3") (pinfunction "NC_3") (pintype "unspecified+no_connect"))
    )
    (net (code "112") (name "unconnected-(U5-Pad6)") (class "Default")
      (node (ref "U5") (pin "6") (pinfunction "6_6") (pintype "unspecified+no_connect"))
    )
    (net (code "113") (name "unconnected-(U6-NC-Pad3)") (class "Default")
      (node (ref "U6") (pin "3") (pinfunction "NC_3") (pintype "unspecified+no_connect"))
    )
    (net (code "114") (name "unconnected-(U6-Pad6)") (class "Default")
      (node (ref "U6") (pin "6") (pinfunction "6_6") (pintype "unspecified+no_connect"))
    )
    (net (code "115") (name "unconnected-(U7-NC-Pad3)") (class "Default")
      (node (ref "U7") (pin "3") (pinfunction "NC_3") (pintype "unspecified+no_connect"))
    )
    (net (code "116") (name "unconnected-(U7-Pad6)") (class "Default")
      (node (ref "U7") (pin "6") (pinfunction "6_6") (pintype "unspecified+no_connect"))
    )
    (net (code "117") (name "unconnected-(U8-NC-Pad3)") (class "Default")
      (node (ref "U8") (pin "3") (pinfunction "NC_3") (pintype "unspecified+no_connect"))
    )
    (net (code "118") (name "unconnected-(U8-Pad6)") (class "Default")
      (node (ref "U8") (pin "6") (pinfunction "6_6") (pintype "unspecified+no_connect"))
    )
  )
)
